# LED.net
KiCad netlist of a schematic drawn in Altium Designer
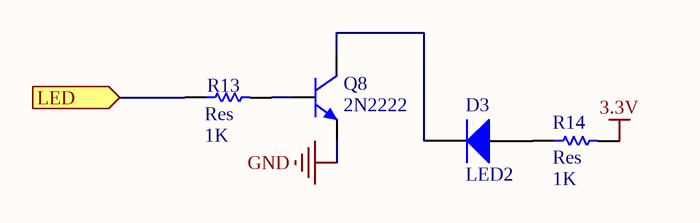
[diagram p0: LED.SchDoc]

(export (version "E")
  (design (tool "Eeschema 10.0.6"))
  (components
    (comp (ref "D3")
      (value "LED2")
      (footprint "2012[0805]")
      (description "1 Amp General Purpose Rectifier")
      (fields (field (name "PUBLISHER") "Altium Limited"))
      (libsource (lib "KN2CLib") (part "Diode"))
    )
    (comp (ref "Q8")
      (value "2N2222")
      (footprint "SOT-23")
      (description "NPN Bipolar Transistor")
      (fields (field (name "PUBLISHER") "Altium Limited"))
      (libsource (lib "KN2CLib") (part "2N2222"))
    )
    (comp (ref "R13")
      (value "Res")
      (footprint "2012[0805]")
      (description "Semiconductor Resistor")
      (fields (field (name "ALTIUM_VALUE") "1K") (field (name "PUBLISHER") "Altium Limited"))
      (libsource (lib "KN2CLib") (part "Res"))
    )
    (comp (ref "R14")
      (value "Res")
      (footprint "2012[0805]")
      (description "Semiconductor Resistor")
      (fields (field (name "ALTIUM_VALUE") "1K") (field (name "PUBLISHER") "Altium Limited"))
      (libsource (lib "KN2CLib") (part "Res"))
    )
  )
  (nets
    (net (code "1") (name "/LED") (class "Default")
      (node (ref "R13") (pin "1") (pinfunction "1_1") (pintype "passive"))
    )
    (net (code "2") (name "3.3V") (class "Default")
      (node (ref "R14") (pin "2") (pinfunction "2_2") (pintype "passive"))
    )
    (net (code "3") (name "GND") (class "Default")
      (node (ref "Q8") (pin "3") (pinfunction "E_3") (pintype "passive"))
    )
    (net (code "4") (name "Net-(D3-A)") (class "Default")
      (node (ref "D3") (pin "1") (pinfunction "A_1") (pintype "passive"))
      (node (ref "R14") (pin "1") (pinfunction "1_1") (pintype "passive"))
    )
    (net (code "5") (name "Net-(D3-K)") (class "Default")
      (node (ref "D3") (pin "2") (pinfunction "K_2") (pintype "passive"))
      (node (ref "Q8") (pin "1") (pinfunction "C_1") (pintype "passive"))
    )
    (net (code "6") (name "Net-(Q8-B)") (class "Default")
      (node (ref "Q8") (pin "2") (pinfunction "B_2") (pintype "passive"))
      (node (ref "R13") (pin "2") (pinfunction "2_2") (pintype "passive"))
    )
  )
)
